# led-rgb.net
KiCad netlist of a schematic drawn in EAGLE
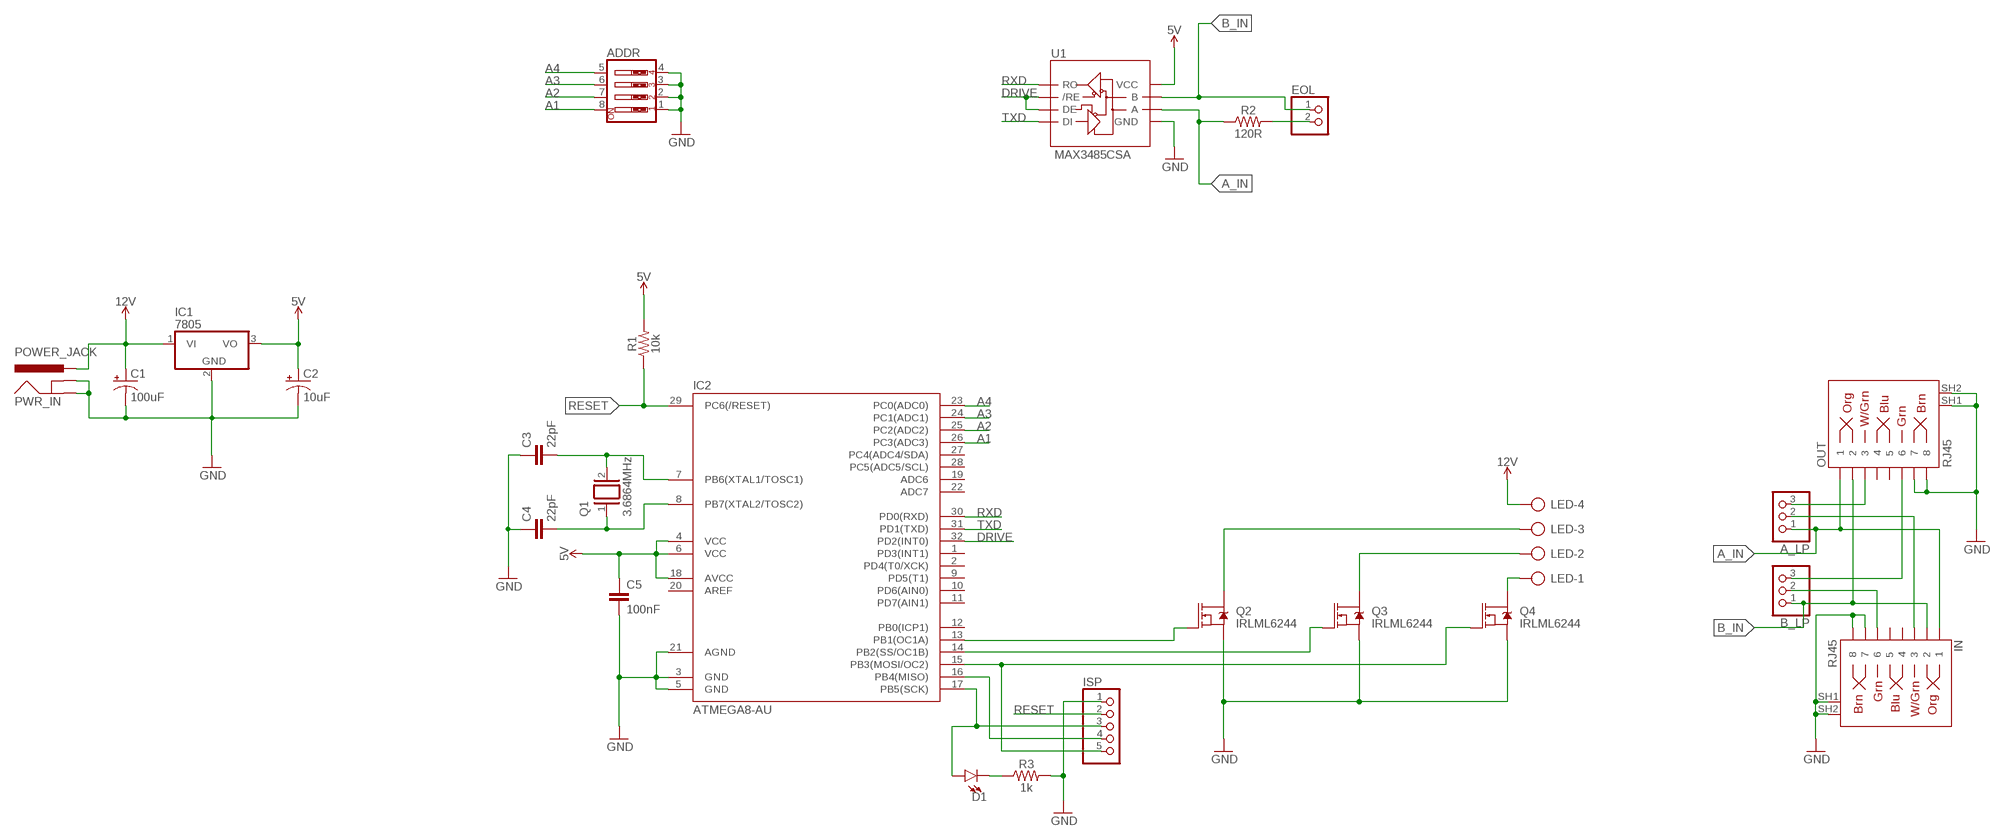
[diagram p0: schematic, sheet 1]

(export (version "E")
  (design (tool "Eeschema 10.0.6"))
  (components
    (comp (ref "ADDR")
      (value "SW_DIP-4")
      (footprint "eagle-import:EDG-04")
      (libsource (lib "eagle-import") (part "SW_DIP-4"))
    )
    (comp (ref "A_LP")
      (value "PINHD-1X3")
      (footprint "eagle-import:1X03")
      (libsource (lib "eagle-import") (part "PINHD-1X3"))
    )
    (comp (ref "B_LP")
      (value "PINHD-1X3")
      (footprint "eagle-import:1X03")
      (libsource (lib "eagle-import") (part "PINHD-1X3"))
    )
    (comp (ref "C1")
      (value "100uF")
      (footprint "eagle-import:CPOL-RADIAL-2.5MM-6.5MM")
      (libsource (lib "eagle-import") (part "100UF-POLAR-RADIAL-2.5MM-25V-20%"))
    )
    (comp (ref "C2")
      (value "10uF")
      (footprint "eagle-import:CPOL-RADIAL-2.5MM-5MM")
      (libsource (lib "eagle-import") (part "10UF-POLAR-RADIAL-2.5MM-25V-20%"))
    )
    (comp (ref "C3")
      (value "22pF")
      (footprint "eagle-import:C0805")
      (libsource (lib "eagle-import") (part "C-EUC0805"))
    )
    (comp (ref "C4")
      (value "22pF")
      (footprint "eagle-import:C0805")
      (libsource (lib "eagle-import") (part "C-EUC0805"))
    )
    (comp (ref "C5")
      (value "100nF")
      (footprint "eagle-import:C0603")
      (fields (field (name "MPN") "C0603X5R1C104K030BC"))
      (libsource (lib "eagle-import") (part "C-EUC0603"))
    )
    (comp (ref "D1")
      (value "LED3MM")
      (footprint "eagle-import:LED_3MM")
      (libsource (lib "eagle-import") (part "LED3MM"))
    )
    (comp (ref "EOL")
      (value "PINHD-1X2")
      (footprint "eagle-import:1X02")
      (fields (field (name "MF") "TYCO ELECTRONICS") (field (name "MPN") "V23026D1021B201 *X020"))
      (libsource (lib "eagle-import") (part "PINHD-1X2"))
    )
    (comp (ref "IC1")
      (value "7805")
      (footprint "eagle-import:TO220V")
      (libsource (lib "eagle-import") (part "78TV12"))
    )
    (comp (ref "IC2")
      (value "ATMEGA8-AU")
      (footprint "eagle-import:TQFP32-08")
      (libsource (lib "eagle-import") (part "ATMEGA8-AU"))
    )
    (comp (ref "IN")
      (value "RJ45")
      (footprint "eagle-import:RJ45-8")
      (libsource (lib "eagle-import") (part "RJ45-8"))
    )
    (comp (ref "ISP")
      (value "PINHD-1X5")
      (footprint "eagle-import:1X05")
      (libsource (lib "eagle-import") (part "PINHD-1X5"))
    )
    (comp (ref "LED")
      (value "AK300/4")
      (footprint "eagle-import:AK300_4")
      (libsource (lib "eagle-import") (part "AK300/4"))
    )
    (comp (ref "OUT")
      (value "RJ45")
      (footprint "eagle-import:RJ45-8")
      (libsource (lib "eagle-import") (part "RJ45-8"))
    )
    (comp (ref "PWR_IN")
      (value "POWER_JACK")
      (footprint "eagle-import:POWER_JACK_PTH")
      (libsource (lib "eagle-import") (part "POWER_JACK"))
    )
    (comp (ref "Q1")
      (value "3.6864MHz")
      (footprint "eagle-import:QS")
      (libsource (lib "eagle-import") (part "XTAL/S"))
    )
    (comp (ref "Q2")
      (value "IRLML6244")
      (footprint "eagle-import:SOT23-3")
      (libsource (lib "eagle-import") (part "MOSFET-NCH-AO3404A"))
    )
    (comp (ref "Q3")
      (value "IRLML6244")
      (footprint "eagle-import:SOT23-3")
      (libsource (lib "eagle-import") (part "MOSFET-NCH-AO3404A"))
    )
    (comp (ref "Q4")
      (value "IRLML6244")
      (footprint "eagle-import:SOT23-3")
      (libsource (lib "eagle-import") (part "MOSFET-NCH-AO3404A"))
    )
    (comp (ref "R1")
      (value "10k")
      (footprint "eagle-import:0603")
      (libsource (lib "eagle-import") (part "10KOHM-0603-1/10W-1%"))
    )
    (comp (ref "R2")
      (value "120R")
      (footprint "eagle-import:0805")
      (libsource (lib "eagle-import") (part "RESISTOR0805"))
    )
    (comp (ref "R3")
      (value "1k")
      (footprint "eagle-import:0603")
      (libsource (lib "eagle-import") (part "1KOHM-0603-1/10W-1%"))
    )
    (comp (ref "U1")
      (value "MAX3485CSA")
      (footprint "eagle-import:SO08")
      (libsource (lib "eagle-import") (part "RS485SOIC"))
    )
  )
  (nets
    (net (code "1") (name "/A1") (class "Default")
      (node (ref "ADDR") (pin "8") (pinfunction "8_8") (pintype "passive"))
      (node (ref "IC2") (pin "26") (pinfunction "PC3(ADC3)_26") (pintype "bidirectional"))
    )
    (net (code "2") (name "/A2") (class "Default")
      (node (ref "ADDR") (pin "7") (pinfunction "7_7") (pintype "passive"))
      (node (ref "IC2") (pin "25") (pinfunction "PC2(ADC2)_25") (pintype "bidirectional"))
    )
    (net (code "3") (name "/A3") (class "Default")
      (node (ref "ADDR") (pin "6") (pinfunction "6_6") (pintype "passive"))
      (node (ref "IC2") (pin "24") (pinfunction "PC1(ADC1)_24") (pintype "bidirectional"))
    )
    (net (code "4") (name "/A4") (class "Default")
      (node (ref "ADDR") (pin "5") (pinfunction "5_5") (pintype "passive"))
      (node (ref "IC2") (pin "23") (pinfunction "PC0(ADC0)_23") (pintype "bidirectional"))
    )
    (net (code "5") (name "/DRIVE") (class "Default")
      (node (ref "IC2") (pin "32") (pinfunction "PD2(INT0)_32") (pintype "bidirectional"))
      (node (ref "U1") (pin "2") (pinfunction "/RE_2") (pintype "bidirectional"))
      (node (ref "U1") (pin "3") (pinfunction "DE_3") (pintype "bidirectional"))
    )
    (net (code "6") (name "/RXD") (class "Default")
      (node (ref "IC2") (pin "30") (pinfunction "PD0(RXD)_30") (pintype "bidirectional"))
      (node (ref "U1") (pin "1") (pinfunction "RO_1") (pintype "bidirectional"))
    )
    (net (code "7") (name "/TXD") (class "Default")
      (node (ref "IC2") (pin "31") (pinfunction "PD1(TXD)_31") (pintype "bidirectional"))
      (node (ref "U1") (pin "4") (pinfunction "DI_4") (pintype "bidirectional"))
    )
    (net (code "8") (name "5V") (class "Default")
      (node (ref "C2") (pin "1") (pinfunction "+_1") (pintype "passive"))
      (node (ref "C5") (pin "1") (pinfunction "1_1") (pintype "passive"))
      (node (ref "IC1") (pin "3") (pinfunction "VO_3") (pintype "passive"))
      (node (ref "IC2") (pin "18") (pinfunction "AVCC_18") (pintype "passive"))
      (node (ref "IC2") (pin "4") (pinfunction "VCC_4") (pintype "power_in"))
      (node (ref "IC2") (pin "6") (pinfunction "VCC_6") (pintype "power_in"))
      (node (ref "R1") (pin "2") (pinfunction "2_2") (pintype "passive"))
      (node (ref "U1") (pin "8") (pinfunction "VCC_8") (pintype "bidirectional"))
    )
    (net (code "9") (name "12V") (class "Default")
      (node (ref "C1") (pin "1") (pinfunction "+_1") (pintype "passive"))
      (node (ref "IC1") (pin "1") (pinfunction "VI_1") (pintype "input"))
      (node (ref "LED") (pin "4") (pinfunction "KL_4") (pintype "passive"))
      (node (ref "PWR_IN") (pin "PWR") (pinfunction "PWR_PWR") (pintype "bidirectional"))
    )
    (net (code "10") (name "A_IN") (class "Default")
      (node (ref "A_LP") (pin "1") (pinfunction "1_1") (pintype "passive"))
      (node (ref "IN") (pin "1") (pinfunction "1_1") (pintype "bidirectional"))
      (node (ref "OUT") (pin "1") (pinfunction "1_1") (pintype "bidirectional"))
      (node (ref "R2") (pin "1") (pinfunction "1_1") (pintype "passive"))
      (node (ref "U1") (pin "6") (pinfunction "A_6") (pintype "bidirectional"))
    )
    (net (code "11") (name "B_IN") (class "Default")
      (node (ref "B_LP") (pin "1") (pinfunction "1_1") (pintype "passive"))
      (node (ref "EOL") (pin "1") (pinfunction "1_1") (pintype "passive"))
      (node (ref "IN") (pin "2") (pinfunction "2_2") (pintype "bidirectional"))
      (node (ref "OUT") (pin "2") (pinfunction "2_2") (pintype "bidirectional"))
      (node (ref "U1") (pin "7") (pinfunction "B_7") (pintype "bidirectional"))
    )
    (net (code "12") (name "GND") (class "Default")
      (node (ref "ADDR") (pin "1") (pinfunction "1_1") (pintype "passive"))
      (node (ref "ADDR") (pin "2") (pinfunction "2_2") (pintype "passive"))
      (node (ref "ADDR") (pin "3") (pinfunction "3_3") (pintype "passive"))
      (node (ref "ADDR") (pin "4") (pinfunction "4_4") (pintype "passive"))
      (node (ref "C1") (pin "2") (pinfunction "-_2") (pintype "passive"))
      (node (ref "C2") (pin "2") (pinfunction "-_2") (pintype "passive"))
      (node (ref "C3") (pin "1") (pinfunction "1_1") (pintype "passive"))
      (node (ref "C4") (pin "1") (pinfunction "1_1") (pintype "passive"))
      (node (ref "C5") (pin "2") (pinfunction "2_2") (pintype "passive"))
      (node (ref "IC1") (pin "2") (pinfunction "GND_2") (pintype "passive"))
      (node (ref "IC2") (pin "21") (pinfunction "AGND_21") (pintype "power_in"))
      (node (ref "IC2") (pin "3") (pinfunction "GND_3") (pintype "power_in"))
      (node (ref "IC2") (pin "5") (pinfunction "GND_5") (pintype "power_in"))
      (node (ref "IN") (pin "7") (pinfunction "7_7") (pintype "bidirectional"))
      (node (ref "IN") (pin "8") (pinfunction "8_8") (pintype "bidirectional"))
      (node (ref "IN") (pin "SH1") (pinfunction "SH1_SH1") (pintype "bidirectional"))
      (node (ref "IN") (pin "SH2") (pinfunction "SH2_SH2") (pintype "bidirectional"))
      (node (ref "ISP") (pin "1") (pinfunction "1_1") (pintype "passive"))
      (node (ref "OUT") (pin "7") (pinfunction "7_7") (pintype "bidirectional"))
      (node (ref "OUT") (pin "8") (pinfunction "8_8") (pintype "bidirectional"))
      (node (ref "OUT") (pin "SH1") (pinfunction "SH1_SH1") (pintype "bidirectional"))
      (node (ref "OUT") (pin "SH2") (pinfunction "SH2_SH2") (pintype "bidirectional"))
      (node (ref "PWR_IN") (pin "GND") (pinfunction "GND_GND") (pintype "bidirectional"))
      (node (ref "PWR_IN") (pin "GNDBREAK") (pinfunction "GNDBREAK_GNDBREAK") (pintype "bidirectional"))
      (node (ref "Q2") (pin "2") (pinfunction "S_2") (pintype "bidirectional"))
      (node (ref "Q3") (pin "2") (pinfunction "S_2") (pintype "bidirectional"))
      (node (ref "Q4") (pin "2") (pinfunction "S_2") (pintype "bidirectional"))
      (node (ref "R3") (pin "2") (pinfunction "2_2") (pintype "passive"))
      (node (ref "U1") (pin "5") (pinfunction "GND_5") (pintype "bidirectional"))
    )
    (net (code "13") (name "Net-(A_LP-Pad2)") (class "Default")
      (node (ref "A_LP") (pin "2") (pinfunction "2_2") (pintype "passive"))
      (node (ref "IN") (pin "3") (pinfunction "3_3") (pintype "bidirectional"))
    )
    (net (code "14") (name "Net-(A_LP-Pad3)") (class "Default")
      (node (ref "A_LP") (pin "3") (pinfunction "3_3") (pintype "passive"))
      (node (ref "OUT") (pin "3") (pinfunction "3_3") (pintype "bidirectional"))
    )
    (net (code "15") (name "Net-(B_LP-Pad2)") (class "Default")
      (node (ref "B_LP") (pin "2") (pinfunction "2_2") (pintype "passive"))
      (node (ref "IN") (pin "6") (pinfunction "6_6") (pintype "bidirectional"))
    )
    (net (code "16") (name "Net-(B_LP-Pad3)") (class "Default")
      (node (ref "B_LP") (pin "3") (pinfunction "3_3") (pintype "passive"))
      (node (ref "OUT") (pin "6") (pinfunction "6_6") (pintype "bidirectional"))
    )
    (net (code "17") (name "Net-(D1-C)") (class "Default")
      (node (ref "D1") (pin "K") (pinfunction "C_K") (pintype "passive"))
      (node (ref "R3") (pin "1") (pinfunction "1_1") (pintype "passive"))
    )
    (net (code "18") (name "Net-(EOL-Pad2)") (class "Default")
      (node (ref "EOL") (pin "2") (pinfunction "2_2") (pintype "passive"))
      (node (ref "R2") (pin "2") (pinfunction "2_2") (pintype "passive"))
    )
    (net (code "19") (name "Net-(IC2-PB1(OC1A))") (class "Default")
      (node (ref "IC2") (pin "13") (pinfunction "PB1(OC1A)_13") (pintype "bidirectional"))
      (node (ref "Q2") (pin "1") (pinfunction "G_1") (pintype "bidirectional"))
    )
    (net (code "20") (name "Net-(IC2-PB2(SS{slash}OC1B))") (class "Default")
      (node (ref "IC2") (pin "14") (pinfunction "PB2(SS/OC1B)_14") (pintype "bidirectional"))
      (node (ref "Q3") (pin "1") (pinfunction "G_1") (pintype "bidirectional"))
    )
    (net (code "21") (name "Net-(IC2-PB3(MOSI{slash}OC2))") (class "Default")
      (node (ref "IC2") (pin "15") (pinfunction "PB3(MOSI/OC2)_15") (pintype "bidirectional"))
      (node (ref "ISP") (pin "5") (pinfunction "5_5") (pintype "passive"))
      (node (ref "Q4") (pin "1") (pinfunction "G_1") (pintype "bidirectional"))
    )
    (net (code "22") (name "Net-(IC2-PB4(MISO))") (class "Default")
      (node (ref "IC2") (pin "16") (pinfunction "PB4(MISO)_16") (pintype "bidirectional"))
      (node (ref "ISP") (pin "4") (pinfunction "4_4") (pintype "passive"))
    )
    (net (code "23") (name "Net-(IC2-PB5(SCK))") (class "Default")
      (node (ref "D1") (pin "A") (pinfunction "A_A") (pintype "passive"))
      (node (ref "IC2") (pin "17") (pinfunction "PB5(SCK)_17") (pintype "bidirectional"))
      (node (ref "ISP") (pin "3") (pinfunction "3_3") (pintype "passive"))
    )
    (net (code "24") (name "Net-(IC2-PB6(XTAL1{slash}TOSC1))") (class "Default")
      (node (ref "C3") (pin "2") (pinfunction "2_2") (pintype "passive"))
      (node (ref "IC2") (pin "7") (pinfunction "PB6(XTAL1/TOSC1)_7") (pintype "bidirectional"))
      (node (ref "Q1") (pin "2") (pinfunction "2_2") (pintype "passive"))
    )
    (net (code "25") (name "Net-(IC2-PB7(XTAL2{slash}TOSC2))") (class "Default")
      (node (ref "C4") (pin "2") (pinfunction "2_2") (pintype "passive"))
      (node (ref "IC2") (pin "8") (pinfunction "PB7(XTAL2/TOSC2)_8") (pintype "bidirectional"))
      (node (ref "Q1") (pin "1") (pinfunction "1_1") (pintype "passive"))
    )
    (net (code "26") (name "Net-(LEDA-KL)") (class "Default")
      (node (ref "LED") (pin "1") (pinfunction "KL_1") (pintype "passive"))
      (node (ref "Q4") (pin "3") (pinfunction "D_3") (pintype "bidirectional"))
    )
    (net (code "27") (name "Net-(LEDB-KL)") (class "Default")
      (node (ref "LED") (pin "2") (pinfunction "KL_2") (pintype "passive"))
      (node (ref "Q3") (pin "3") (pinfunction "D_3") (pintype "bidirectional"))
    )
    (net (code "28") (name "Net-(LEDC-KL)") (class "Default")
      (node (ref "LED") (pin "3") (pinfunction "KL_3") (pintype "passive"))
      (node (ref "Q2") (pin "3") (pinfunction "D_3") (pintype "bidirectional"))
    )
    (net (code "29") (name "RESET") (class "Default")
      (node (ref "IC2") (pin "29") (pinfunction "PC6(/RESET)_29") (pintype "bidirectional"))
      (node (ref "ISP") (pin "2") (pinfunction "2_2") (pintype "passive"))
      (node (ref "R1") (pin "1") (pinfunction "1_1") (pintype "passive"))
    )
    (net (code "30") (name "unconnected-(IC2-ADC6-Pad19)") (class "Default")
      (node (ref "IC2") (pin "19") (pinfunction "ADC6_19") (pintype "passive"))
    )
    (net (code "31") (name "unconnected-(IC2-ADC7-Pad22)") (class "Default")
      (node (ref "IC2") (pin "22") (pinfunction "ADC7_22") (pintype "passive"))
    )
    (net (code "32") (name "unconnected-(IC2-AREF-Pad20)") (class "Default")
      (node (ref "IC2") (pin "20") (pinfunction "AREF_20") (pintype "passive"))
    )
    (net (code "33") (name "unconnected-(IC2-PB0(ICP1)-Pad12)") (class "Default")
      (node (ref "IC2") (pin "12") (pinfunction "PB0(ICP1)_12") (pintype "bidirectional"))
    )
    (net (code "34") (name "unconnected-(IC2-PC4(ADC4{slash}SDA)-Pad27)") (class "Default")
      (node (ref "IC2") (pin "27") (pinfunction "PC4(ADC4/SDA)_27") (pintype "bidirectional"))
    )
    (net (code "35") (name "unconnected-(IC2-PC5(ADC5{slash}SCL)-Pad28)") (class "Default")
      (node (ref "IC2") (pin "28") (pinfunction "PC5(ADC5/SCL)_28") (pintype "bidirectional"))
    )
    (net (code "36") (name "unconnected-(IC2-PD3(INT1)-Pad1)") (class "Default")
      (node (ref "IC2") (pin "1") (pinfunction "PD3(INT1)_1") (pintype "bidirectional"))
    )
    (net (code "37") (name "unconnected-(IC2-PD4(T0{slash}XCK)-Pad2)") (class "Default")
      (node (ref "IC2") (pin "2") (pinfunction "PD4(T0/XCK)_2") (pintype "bidirectional"))
    )
    (net (code "38") (name "unconnected-(IC2-PD5(T1)-Pad9)") (class "Default")
      (node (ref "IC2") (pin "9") (pinfunction "PD5(T1)_9") (pintype "bidirectional"))
    )
    (net (code "39") (name "unconnected-(IC2-PD6(AIN0)-Pad10)") (class "Default")
      (node (ref "IC2") (pin "10") (pinfunction "PD6(AIN0)_10") (pintype "bidirectional"))
    )
    (net (code "40") (name "unconnected-(IC2-PD7(AIN1)-Pad11)") (class "Default")
      (node (ref "IC2") (pin "11") (pinfunction "PD7(AIN1)_11") (pintype "bidirectional"))
    )
    (net (code "41") (name "unconnected-(IN-Pad4)") (class "Default")
      (node (ref "IN") (pin "4") (pinfunction "4_4") (pintype "bidirectional"))
    )
    (net (code "42") (name "unconnected-(IN-Pad5)") (class "Default")
      (node (ref "IN") (pin "5") (pinfunction "5_5") (pintype "bidirectional"))
    )
    (net (code "43") (name "unconnected-(OUT-Pad4)") (class "Default")
      (node (ref "OUT") (pin "4") (pinfunction "4_4") (pintype "bidirectional"))
    )
    (net (code "44") (name "unconnected-(OUT-Pad5)") (class "Default")
      (node (ref "OUT") (pin "5") (pinfunction "5_5") (pintype "bidirectional"))
    )
  )
)
